# attiny45-microcontrol-v2_2-notworking.net
KiCad netlist of a schematic drawn in EAGLE
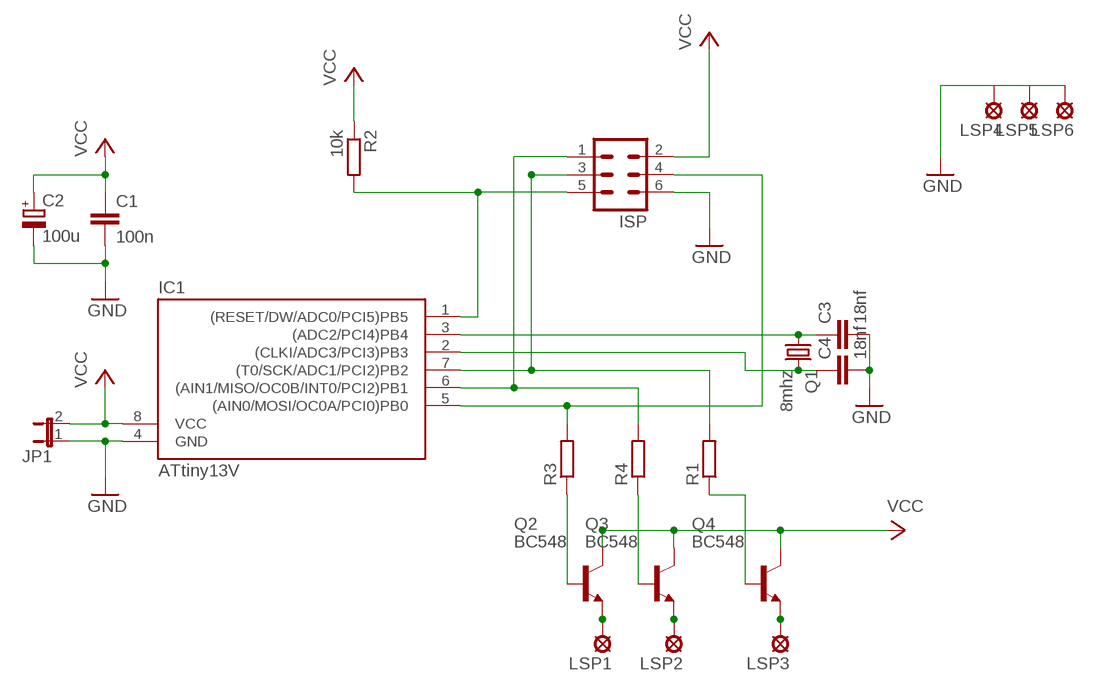
[diagram p0: schematic, sheet 1]

(export (version "E")
  (design (tool "Eeschema 10.0.6"))
  (components
    (comp (ref "C1")
      (value "100n")
      (footprint "eagle-import:C025-025X050")
      (libsource (lib "eagle-import") (part "C-EU025-025X050"))
    )
    (comp (ref "C2")
      (value "100u")
      (footprint "eagle-import:E2,5-6E")
      (libsource (lib "eagle-import") (part "CPOL-EUE2,5-6E"))
    )
    (comp (ref "C3")
      (value "18nf")
      (footprint "eagle-import:C5B2.5")
      (libsource (lib "eagle-import") (part "C5/2.5"))
    )
    (comp (ref "C4")
      (value "18nf")
      (footprint "eagle-import:C5B2.5")
      (libsource (lib "eagle-import") (part "C5/2.5"))
    )
    (comp (ref "IC1")
      (value "ATtiny13V")
      (footprint "eagle-import:DIL08")
      (libsource (lib "eagle-import") (part "ATTINY13P-20"))
    )
    (comp (ref "ISP")
      (value "MA03-2")
      (footprint "eagle-import:MA03-2")
      (libsource (lib "eagle-import") (part "MA03-2"))
    )
    (comp (ref "JP1")
      (value "JP1E")
      (footprint "eagle-import:JP1")
      (libsource (lib "eagle-import") (part "JP1E"))
    )
    (comp (ref "LSP1")
      (value "LSP10")
      (footprint "eagle-import:LSP10")
      (libsource (lib "eagle-import") (part "LSP10"))
    )
    (comp (ref "LSP2")
      (value "LSP10")
      (footprint "eagle-import:LSP10")
      (libsource (lib "eagle-import") (part "LSP10"))
    )
    (comp (ref "LSP3")
      (value "LSP10")
      (footprint "eagle-import:LSP10")
      (libsource (lib "eagle-import") (part "LSP10"))
    )
    (comp (ref "LSP4")
      (value "LSP10")
      (footprint "eagle-import:LSP10")
      (libsource (lib "eagle-import") (part "LSP10"))
    )
    (comp (ref "LSP5")
      (value "LSP10")
      (footprint "eagle-import:LSP10")
      (libsource (lib "eagle-import") (part "LSP10"))
    )
    (comp (ref "LSP6")
      (value "LSP10")
      (footprint "eagle-import:LSP10")
      (libsource (lib "eagle-import") (part "LSP10"))
    )
    (comp (ref "Q1")
      (value "8mhz")
      (footprint "eagle-import:HC18U-V")
      (libsource (lib "eagle-import") (part "CRYSTALHC18U-V"))
    )
    (comp (ref "Q2")
      (value "BC548")
      (footprint "eagle-import:TO92-EBC")
      (libsource (lib "eagle-import") (part "BC548"))
    )
    (comp (ref "Q3")
      (value "BC548")
      (footprint "eagle-import:TO92-EBC")
      (libsource (lib "eagle-import") (part "BC548"))
    )
    (comp (ref "Q4")
      (value "BC548")
      (footprint "eagle-import:TO92-EBC")
      (libsource (lib "eagle-import") (part "BC548"))
    )
    (comp (ref "R1")
      (value "R-EU_0204/5")
      (footprint "eagle-import:0204_5")
      (libsource (lib "eagle-import") (part "R-EU_0204/5"))
    )
    (comp (ref "R2")
      (value "10k")
      (footprint "eagle-import:0309_12")
      (libsource (lib "eagle-import") (part "R-EU_0309/12"))
    )
    (comp (ref "R3")
      (value "R-EU_0204/5")
      (footprint "eagle-import:0204_5")
      (libsource (lib "eagle-import") (part "R-EU_0204/5"))
    )
    (comp (ref "R4")
      (value "R-EU_0204/5")
      (footprint "eagle-import:0204_5")
      (libsource (lib "eagle-import") (part "R-EU_0204/5"))
    )
  )
  (nets
    (net (code "1") (name "GND") (class "Default")
      (node (ref "C1") (pin "2") (pinfunction "2_2") (pintype "passive"))
      (node (ref "C2") (pin "-") (pinfunction "-_-") (pintype "passive"))
      (node (ref "C3") (pin "2") (pinfunction "2_2") (pintype "passive"))
      (node (ref "C4") (pin "2") (pinfunction "2_2") (pintype "passive"))
      (node (ref "IC1") (pin "4") (pinfunction "GND_4") (pintype "power_in"))
      (node (ref "ISP") (pin "6") (pinfunction "6_6") (pintype "passive"))
      (node (ref "JP1") (pin "1") (pinfunction "1_1") (pintype "passive"))
      (node (ref "LSP4") (pin "MP") (pinfunction "MP_MP") (pintype "passive"))
      (node (ref "LSP5") (pin "MP") (pinfunction "MP_MP") (pintype "passive"))
      (node (ref "LSP6") (pin "MP") (pinfunction "MP_MP") (pintype "passive"))
    )
    (net (code "2") (name "Net-(IC1-(ADC2{slash}PCI4)PB4)") (class "Default")
      (node (ref "C3") (pin "1") (pinfunction "1_1") (pintype "passive"))
      (node (ref "IC1") (pin "3") (pinfunction "(ADC2/PCI4)PB4_3") (pintype "bidirectional"))
      (node (ref "Q1") (pin "1") (pinfunction "1_1") (pintype "passive"))
    )
    (net (code "3") (name "Net-(IC1-(AIN0{slash}MOSI{slash}OC0A{slash}PCI0)PB0)") (class "Default")
      (node (ref "IC1") (pin "5") (pinfunction "(AIN0/MOSI/OC0A/PCI0)PB0_5") (pintype "bidirectional"))
      (node (ref "ISP") (pin "4") (pinfunction "4_4") (pintype "passive"))
      (node (ref "R3") (pin "2") (pinfunction "2_2") (pintype "passive"))
    )
    (net (code "4") (name "Net-(IC1-(AIN1{slash}MISO{slash}OC0B{slash}INT0{slash}PCI2)PB1)") (class "Default")
      (node (ref "IC1") (pin "6") (pinfunction "(AIN1/MISO/OC0B/INT0/PCI2)PB1_6") (pintype "bidirectional"))
      (node (ref "ISP") (pin "1") (pinfunction "1_1") (pintype "passive"))
      (node (ref "R4") (pin "2") (pinfunction "2_2") (pintype "passive"))
    )
    (net (code "5") (name "Net-(IC1-(CLKI{slash}ADC3{slash}PCI3)PB3)") (class "Default")
      (node (ref "C4") (pin "1") (pinfunction "1_1") (pintype "passive"))
      (node (ref "IC1") (pin "2") (pinfunction "(CLKI/ADC3/PCI3)PB3_2") (pintype "bidirectional"))
      (node (ref "Q1") (pin "2") (pinfunction "2_2") (pintype "passive"))
    )
    (net (code "6") (name "Net-(IC1-(RESET{slash}DW{slash}ADC0{slash}PCI5)PB5)") (class "Default")
      (node (ref "IC1") (pin "1") (pinfunction "(RESET/DW/ADC0/PCI5)PB5_1") (pintype "bidirectional"))
      (node (ref "ISP") (pin "5") (pinfunction "5_5") (pintype "passive"))
      (node (ref "R2") (pin "2") (pinfunction "2_2") (pintype "passive"))
    )
    (net (code "7") (name "Net-(IC1-(T0{slash}SCK{slash}ADC1{slash}PCI2)PB2)") (class "Default")
      (node (ref "IC1") (pin "7") (pinfunction "(T0/SCK/ADC1/PCI2)PB2_7") (pintype "bidirectional"))
      (node (ref "ISP") (pin "3") (pinfunction "3_3") (pintype "passive"))
      (node (ref "R1") (pin "2") (pinfunction "2_2") (pintype "passive"))
    )
    (net (code "8") (name "Net-(LSP1-PadMP)") (class "Default")
      (node (ref "LSP1") (pin "MP") (pinfunction "MP_MP") (pintype "passive"))
      (node (ref "Q2") (pin "E") (pinfunction "E_E") (pintype "passive"))
    )
    (net (code "9") (name "Net-(LSP2-PadMP)") (class "Default")
      (node (ref "LSP2") (pin "MP") (pinfunction "MP_MP") (pintype "passive"))
      (node (ref "Q3") (pin "E") (pinfunction "E_E") (pintype "passive"))
    )
    (net (code "10") (name "Net-(LSP3-PadMP)") (class "Default")
      (node (ref "LSP3") (pin "MP") (pinfunction "MP_MP") (pintype "passive"))
      (node (ref "Q4") (pin "E") (pinfunction "E_E") (pintype "passive"))
    )
    (net (code "11") (name "Net-(Q2-PadB)") (class "Default")
      (node (ref "Q2") (pin "B") (pinfunction "B_B") (pintype "passive"))
      (node (ref "R3") (pin "1") (pinfunction "1_1") (pintype "passive"))
    )
    (net (code "12") (name "Net-(Q3-PadB)") (class "Default")
      (node (ref "Q3") (pin "B") (pinfunction "B_B") (pintype "passive"))
      (node (ref "R4") (pin "1") (pinfunction "1_1") (pintype "passive"))
    )
    (net (code "13") (name "Net-(Q4-PadB)") (class "Default")
      (node (ref "Q4") (pin "B") (pinfunction "B_B") (pintype "passive"))
      (node (ref "R1") (pin "1") (pinfunction "1_1") (pintype "passive"))
    )
    (net (code "14") (name "VCC") (class "Default")
      (node (ref "C1") (pin "1") (pinfunction "1_1") (pintype "passive"))
      (node (ref "C2") (pin "+") (pinfunction "+_+") (pintype "passive"))
      (node (ref "IC1") (pin "8") (pinfunction "VCC_8") (pintype "power_in"))
      (node (ref "ISP") (pin "2") (pinfunction "2_2") (pintype "passive"))
      (node (ref "JP1") (pin "2") (pinfunction "2_2") (pintype "passive"))
      (node (ref "Q2") (pin "C") (pinfunction "C_C") (pintype "passive"))
      (node (ref "Q3") (pin "C") (pinfunction "C_C") (pintype "passive"))
      (node (ref "Q4") (pin "C") (pinfunction "C_C") (pintype "passive"))
      (node (ref "R2") (pin "1") (pinfunction "1_1") (pintype "passive"))
    )
  )
)
